# OSO-BILI-A1-00.net
KiCad netlist of a schematic drawn in EAGLE
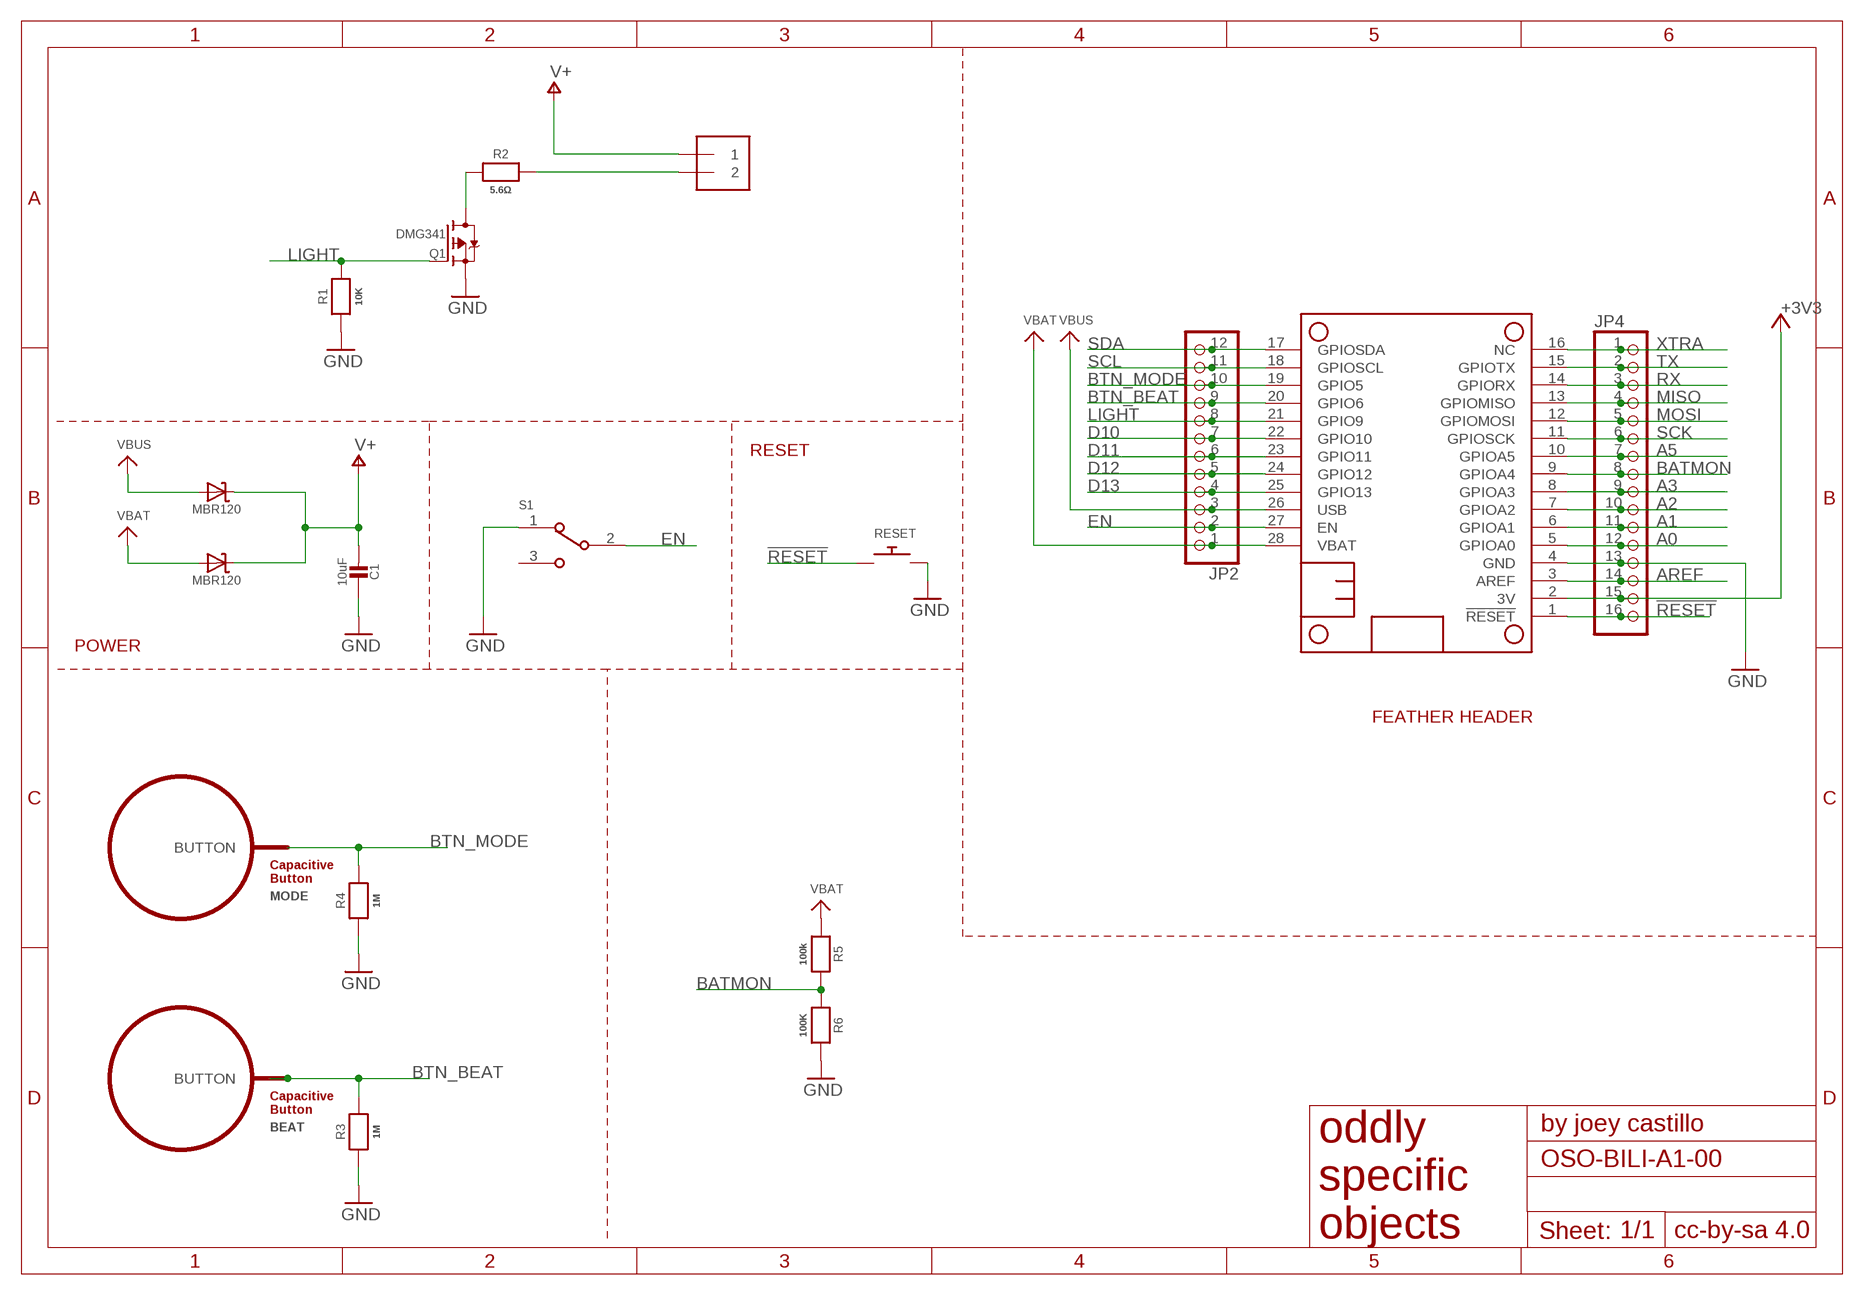
[diagram p0: schematic, sheet 1]

(export (version "E")
  (design (tool "Eeschema 10.0.6"))
  (components
    (comp (ref "BEAT")
      (value "BUTTON_PASSIVE12MM")
      (footprint "eagle-import:BUTTON_PASSIVE_12MM")
      (libsource (lib "eagle-import") (part "BUTTON_PASSIVE12MM"))
    )
    (comp (ref "C1")
      (value "10uF")
      (footprint "eagle-import:0805-NO")
      (libsource (lib "eagle-import") (part "CAP_CERAMIC0805-NOOUTLINE"))
    )
    (comp (ref "D1")
      (value "MBR120")
      (footprint "eagle-import:SOD-123")
      (libsource (lib "eagle-import") (part "DIODE-SCHOTTKYSOD-123"))
    )
    (comp (ref "D2")
      (value "MBR120")
      (footprint "eagle-import:SOD-123")
      (libsource (lib "eagle-import") (part "DIODE-SCHOTTKYSOD-123"))
    )
    (comp (ref "J1")
      (value "1X25MM")
      (footprint "eagle-import:1X2-5MM")
      (libsource (lib "eagle-import") (part "1X25MM"))
    )
    (comp (ref "JP2")
      (value "HEADER-1X12")
      (footprint "eagle-import:1X12_ROUND")
      (libsource (lib "eagle-import") (part "HEADER-1X12"))
    )
    (comp (ref "JP4")
      (value "HEADER-1X16ROUND")
      (footprint "eagle-import:1X16_ROUND")
      (libsource (lib "eagle-import") (part "HEADER-1X16ROUND"))
    )
    (comp (ref "MODE")
      (value "BUTTON_PASSIVE8MM")
      (footprint "eagle-import:BUTTON_PASSIVE_8MM")
      (libsource (lib "eagle-import") (part "BUTTON_PASSIVE8MM"))
    )
    (comp (ref "MS1")
      (value "FEATHERWING")
      (footprint "eagle-import:FEATHERWING")
      (libsource (lib "eagle-import") (part "FEATHERWING"))
    )
    (comp (ref "Q1")
      (value "DMG341")
      (footprint "eagle-import:SOT23-R")
      (libsource (lib "eagle-import") (part "MOSFET-P"))
    )
    (comp (ref "R1")
      (value "10K")
      (footprint "eagle-import:0805-NO")
      (libsource (lib "eagle-import") (part "RESISTOR0805_NOOUTLINE"))
    )
    (comp (ref "R2")
      (value "5.6Ω")
      (footprint "eagle-import:2012")
      (libsource (lib "eagle-import") (part "RESISTOR2012"))
    )
    (comp (ref "R3")
      (value "1M")
      (footprint "eagle-import:0805-NO")
      (libsource (lib "eagle-import") (part "RESISTOR0805_NOOUTLINE"))
    )
    (comp (ref "R4")
      (value "1M")
      (footprint "eagle-import:0805-NO")
      (libsource (lib "eagle-import") (part "RESISTOR0805_NOOUTLINE"))
    )
    (comp (ref "R5")
      (value "100k")
      (footprint "eagle-import:0805_10MGAP")
      (libsource (lib "eagle-import") (part "RESISTOR0805_10MGAP"))
    )
    (comp (ref "R6")
      (value "100K")
      (footprint "eagle-import:0805-NO")
      (libsource (lib "eagle-import") (part "RESISTOR0805_NOOUTLINE"))
    )
    (comp (ref "RESET")
      (value "SWITCH_PUSHBUTTONC&K_KSS")
      (footprint "eagle-import:BTN_CK_KSS")
      (libsource (lib "eagle-import") (part "SWITCH_PUSHBUTTONC&K_KSS"))
    )
    (comp (ref "S1")
      (value "JS102011SAQN")
      (footprint "eagle-import:SW_JS102011SAQN")
      (fields (field (name "DIGI-KEY_PART_NUMBER") "401-1999-1-ND") (field (name "MF") "C&K"))
      (libsource (lib "eagle-import") (part "JS102011SAQN"))
    )
  )
  (nets
    (net (code "1") (name "+3V3") (class "Default")
      (node (ref "JP4") (pin "15") (pinfunction "15_15") (pintype "passive"))
      (node (ref "MS1") (pin "2") (pinfunction "3V_2") (pintype "power_in"))
    )
    (net (code "2") (name "/A0") (class "Default")
      (node (ref "JP4") (pin "12") (pinfunction "12_12") (pintype "passive"))
      (node (ref "MS1") (pin "5") (pinfunction "GPIOA0_5") (pintype "bidirectional"))
    )
    (net (code "3") (name "/A1") (class "Default")
      (node (ref "JP4") (pin "11") (pinfunction "11_11") (pintype "passive"))
      (node (ref "MS1") (pin "6") (pinfunction "GPIOA1_6") (pintype "bidirectional"))
    )
    (net (code "4") (name "/A2") (class "Default")
      (node (ref "JP4") (pin "10") (pinfunction "10_10") (pintype "passive"))
      (node (ref "MS1") (pin "7") (pinfunction "GPIOA2_7") (pintype "bidirectional"))
    )
    (net (code "5") (name "/A3") (class "Default")
      (node (ref "JP4") (pin "9") (pinfunction "9_9") (pintype "passive"))
      (node (ref "MS1") (pin "8") (pinfunction "GPIOA3_8") (pintype "bidirectional"))
    )
    (net (code "6") (name "/A5") (class "Default")
      (node (ref "JP4") (pin "7") (pinfunction "7_7") (pintype "passive"))
      (node (ref "MS1") (pin "10") (pinfunction "GPIOA5_10") (pintype "bidirectional"))
    )
    (net (code "7") (name "/AREF") (class "Default")
      (node (ref "JP4") (pin "14") (pinfunction "14_14") (pintype "passive"))
      (node (ref "MS1") (pin "3") (pinfunction "AREF_3") (pintype "passive"))
    )
    (net (code "8") (name "/BATMON") (class "Default")
      (node (ref "JP4") (pin "8") (pinfunction "8_8") (pintype "passive"))
      (node (ref "MS1") (pin "9") (pinfunction "GPIOA4_9") (pintype "bidirectional"))
      (node (ref "R5") (pin "2") (pinfunction "2_2") (pintype "passive"))
      (node (ref "R6") (pin "1") (pinfunction "1_1") (pintype "passive"))
    )
    (net (code "9") (name "/BTN_BEAT") (class "Default")
      (node (ref "BEAT") (pin "BUTTON") (pinfunction "BUTTON_BUTTON") (pintype "passive"))
      (node (ref "JP2") (pin "9") (pinfunction "9_9") (pintype "passive"))
      (node (ref "MS1") (pin "20") (pinfunction "GPIO6_20") (pintype "bidirectional"))
      (node (ref "R3") (pin "2") (pinfunction "2_2") (pintype "passive"))
    )
    (net (code "10") (name "/BTN_MODE") (class "Default")
      (node (ref "JP2") (pin "10") (pinfunction "10_10") (pintype "passive"))
      (node (ref "MODE") (pin "BUTTON") (pinfunction "BUTTON_BUTTON") (pintype "passive"))
      (node (ref "MS1") (pin "19") (pinfunction "GPIO5_19") (pintype "bidirectional"))
      (node (ref "R4") (pin "2") (pinfunction "2_2") (pintype "passive"))
    )
    (net (code "11") (name "/D10") (class "Default")
      (node (ref "JP2") (pin "7") (pinfunction "7_7") (pintype "passive"))
      (node (ref "MS1") (pin "22") (pinfunction "GPIO10_22") (pintype "bidirectional"))
    )
    (net (code "12") (name "/D11") (class "Default")
      (node (ref "JP2") (pin "6") (pinfunction "6_6") (pintype "passive"))
      (node (ref "MS1") (pin "23") (pinfunction "GPIO11_23") (pintype "bidirectional"))
    )
    (net (code "13") (name "/D12") (class "Default")
      (node (ref "JP2") (pin "5") (pinfunction "5_5") (pintype "passive"))
      (node (ref "MS1") (pin "24") (pinfunction "GPIO12_24") (pintype "bidirectional"))
    )
    (net (code "14") (name "/D13") (class "Default")
      (node (ref "JP2") (pin "4") (pinfunction "4_4") (pintype "passive"))
      (node (ref "MS1") (pin "25") (pinfunction "GPIO13_25") (pintype "bidirectional"))
    )
    (net (code "15") (name "/EN") (class "Default")
      (node (ref "JP2") (pin "2") (pinfunction "2_2") (pintype "passive"))
      (node (ref "MS1") (pin "27") (pinfunction "EN_27") (pintype "passive"))
      (node (ref "S1") (pin "2") (pinfunction "2_2") (pintype "passive"))
    )
    (net (code "16") (name "/LIGHT") (class "Default")
      (node (ref "JP2") (pin "8") (pinfunction "8_8") (pintype "passive"))
      (node (ref "MS1") (pin "21") (pinfunction "GPIO9_21") (pintype "bidirectional"))
      (node (ref "Q1") (pin "1") (pinfunction "G_1") (pintype "passive"))
      (node (ref "R1") (pin "2") (pinfunction "2_2") (pintype "passive"))
    )
    (net (code "17") (name "/MISO") (class "Default")
      (node (ref "JP4") (pin "4") (pinfunction "4_4") (pintype "passive"))
      (node (ref "MS1") (pin "13") (pinfunction "GPIOMISO_13") (pintype "bidirectional"))
    )
    (net (code "18") (name "/MOSI") (class "Default")
      (node (ref "JP4") (pin "5") (pinfunction "5_5") (pintype "passive"))
      (node (ref "MS1") (pin "12") (pinfunction "GPIOMOSI_12") (pintype "bidirectional"))
    )
    (net (code "19") (name "/RX") (class "Default")
      (node (ref "JP4") (pin "3") (pinfunction "3_3") (pintype "passive"))
      (node (ref "MS1") (pin "14") (pinfunction "GPIORX_14") (pintype "bidirectional"))
    )
    (net (code "20") (name "/SCK") (class "Default")
      (node (ref "JP4") (pin "6") (pinfunction "6_6") (pintype "passive"))
      (node (ref "MS1") (pin "11") (pinfunction "GPIOSCK_11") (pintype "bidirectional"))
    )
    (net (code "21") (name "/SCL") (class "Default")
      (node (ref "JP2") (pin "11") (pinfunction "11_11") (pintype "passive"))
      (node (ref "MS1") (pin "18") (pinfunction "GPIOSCL_18") (pintype "bidirectional"))
    )
    (net (code "22") (name "/SDA") (class "Default")
      (node (ref "JP2") (pin "12") (pinfunction "12_12") (pintype "passive"))
      (node (ref "MS1") (pin "17") (pinfunction "GPIOSDA_17") (pintype "bidirectional"))
    )
    (net (code "23") (name "/TX") (class "Default")
      (node (ref "JP4") (pin "2") (pinfunction "2_2") (pintype "passive"))
      (node (ref "MS1") (pin "15") (pinfunction "GPIOTX_15") (pintype "bidirectional"))
    )
    (net (code "24") (name "/XTRA") (class "Default")
      (node (ref "JP4") (pin "1") (pinfunction "1_1") (pintype "passive"))
      (node (ref "MS1") (pin "16") (pinfunction "NC_16") (pintype "passive"))
    )
    (net (code "25") (name "/~{RESET}") (class "Default")
      (node (ref "JP4") (pin "16") (pinfunction "16_16") (pintype "passive"))
      (node (ref "MS1") (pin "1") (pinfunction "~{RESET}_1") (pintype "input"))
      (node (ref "RESET") (pin "P$1") (pinfunction "P$1_P$1") (pintype "passive"))
    )
    (net (code "26") (name "GND") (class "Default")
      (node (ref "C1") (pin "1") (pinfunction "1_1") (pintype "passive"))
      (node (ref "JP4") (pin "13") (pinfunction "13_13") (pintype "passive"))
      (node (ref "MS1") (pin "4") (pinfunction "GND_4") (pintype "power_in"))
      (node (ref "Q1") (pin "2") (pinfunction "S_2") (pintype "passive"))
      (node (ref "R1") (pin "1") (pinfunction "1_1") (pintype "passive"))
      (node (ref "R3") (pin "1") (pinfunction "1_1") (pintype "passive"))
      (node (ref "R4") (pin "1") (pinfunction "1_1") (pintype "passive"))
      (node (ref "R6") (pin "2") (pinfunction "2_2") (pintype "passive"))
      (node (ref "RESET") (pin "P$2") (pinfunction "P$2_P$2") (pintype "passive"))
      (node (ref "S1") (pin "1") (pinfunction "1_1") (pintype "passive"))
    )
    (net (code "27") (name "Net-(J1-Pad2)") (class "Default")
      (node (ref "J1") (pin "2") (pinfunction "2_2") (pintype "passive"))
      (node (ref "R2") (pin "2") (pinfunction "2_2") (pintype "passive"))
    )
    (net (code "28") (name "Net-(Q1-D)") (class "Default")
      (node (ref "Q1") (pin "3") (pinfunction "D_3") (pintype "passive"))
      (node (ref "R2") (pin "1") (pinfunction "1_1") (pintype "passive"))
    )
    (net (code "29") (name "V+") (class "Default")
      (node (ref "C1") (pin "2") (pinfunction "2_2") (pintype "passive"))
      (node (ref "D1") (pin "C") (pinfunction "C_C") (pintype "passive"))
      (node (ref "D2") (pin "C") (pinfunction "C_C") (pintype "passive"))
      (node (ref "J1") (pin "1") (pinfunction "1_1") (pintype "passive"))
    )
    (net (code "30") (name "VBAT") (class "Default")
      (node (ref "D2") (pin "A") (pinfunction "A_A") (pintype "passive"))
      (node (ref "JP2") (pin "1") (pinfunction "1_1") (pintype "passive"))
      (node (ref "MS1") (pin "28") (pinfunction "VBAT_28") (pintype "power_in"))
      (node (ref "R5") (pin "1") (pinfunction "1_1") (pintype "passive"))
    )
    (net (code "31") (name "VBUS") (class "Default")
      (node (ref "D1") (pin "A") (pinfunction "A_A") (pintype "passive"))
      (node (ref "JP2") (pin "3") (pinfunction "3_3") (pintype "passive"))
      (node (ref "MS1") (pin "26") (pinfunction "USB_26") (pintype "power_in"))
    )
    (net (code "32") (name "unconnected-(S1-Pad3)") (class "Default")
      (node (ref "S1") (pin "3") (pinfunction "3_3") (pintype "passive"))
    )
  )
)
